# Sch_remote.net
KiCad netlist of a schematic drawn in Altium Designer
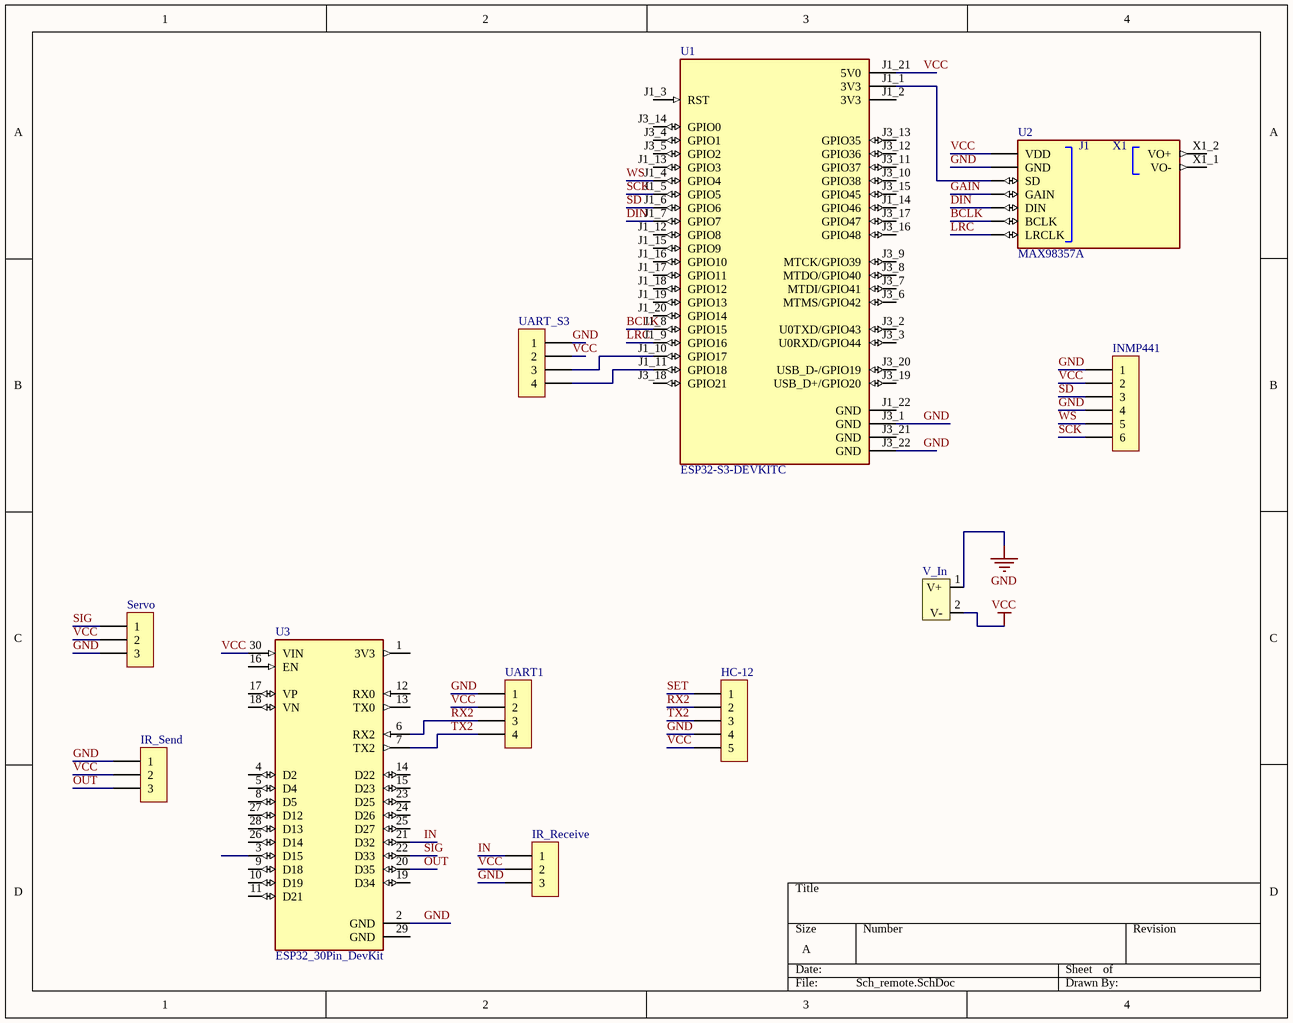
[diagram p0: Sch_remote.SchDoc]

(export (version "E")
  (design (tool "Eeschema 10.0.6"))
  (components
    (comp (ref "HC-12")
      (value "HC-12")
      (footprint "XH2.54M-5")
      (description "Cắm")
      (libsource (lib "Altium_Lib_by_KhueNguyenCreator") (part "Header 5P 2.54 Duc Thang"))
    )
    (comp (ref "INMP441")
      (value "INMP441")
      (footprint "XH2.54M-6")
      (description "Cắm")
      (libsource (lib "Altium_Lib_by_KhueNguyenCreator") (part "Header 6P 2.54 Duc Thang"))
    )
    (comp (ref "IR_Receive")
      (value "IR_Receive")
      (footprint "XH2.54M-3")
      (description "Cắm")
      (libsource (lib "Altium_Lib_by_KhueNguyenCreator") (part "Header 3P 2.54 Duc Thang"))
    )
    (comp (ref "IR_Send")
      (value "IR_Send")
      (footprint "XH2.54M-3")
      (description "Cắm")
      (libsource (lib "Altium_Lib_by_KhueNguyenCreator") (part "Header 3P 2.54 Duc Thang"))
    )
    (comp (ref "Servo")
      (value "Servo")
      (footprint "XH2.54M-3")
      (description "Cắm")
      (libsource (lib "Altium_Lib_by_KhueNguyenCreator") (part "Header 3P 2.54 Duc Thang"))
    )
    (comp (ref "U1")
      (value "ESP32-S3-DEVKITC")
      (footprint "ESP32_S3_DEV_KIT")
      (fields (field (name "MF") "Espressif Systems") (field (name "MP") "ESP32-S3-DEVKITC-1U-N8R8"))
      (libsource (lib "Schlib1") (part "ESP32-S3-DEVKITC"))
    )
    (comp (ref "U2")
      (value "MAX98357A")
      (footprint "MAX98357")
      (description "MAX98357A - 1-Channel (Mono) Output Class D Audio Amplifier Evaluation Board")
      (fields (field (name "MF") "Adafruit") (field (name "MP") "3006"))
      (libsource (lib "Schlib1") (part "MAX98357A"))
    )
    (comp (ref "U3")
      (value "ESP32_30Pin_DevKit")
      (footprint "MODULE_ESP32_DEVKIT_V1")
      (fields (field (name "MF") "Do it") (field (name "MP") "ESP32-DEVKIT-V1"))
      (libsource (lib "Schlib1") (part "ESP32_30Pin_DevKit"))
    )
    (comp (ref "UART1")
      (value "UART1")
      (footprint "Header 4P DC 2.54")
      (description "Cắm")
      (libsource (lib "Altium_Lib_by_KhueNguyenCreator") (part "Header 4P 2.54 Duc Cong"))
    )
    (comp (ref "UART_S3")
      (value "UART_S3")
      (footprint "Header 4P DC 2.54")
      (description "Cắm")
      (libsource (lib "") (part "Header 4P 2.54 Duc Cong_1"))
    )
    (comp (ref "V_In")
      (value "V_In")
      (footprint "header_2_power")
      (libsource (lib "Schlib1") (part "Header_2pin"))
    )
  )
  (nets
    (net (code "1") (name "/BCLK") (class "Default")
      (node (ref "U1") (pin "J1_8") (pinfunction "GPIO15_J1_8") (pintype "bidirectional"))
      (node (ref "U2") (pin "6") (pinfunction "BCLK_6") (pintype "bidirectional"))
    )
    (net (code "2") (name "/DIN") (class "Default")
      (node (ref "U1") (pin "J1_7") (pinfunction "GPIO7_J1_7") (pintype "bidirectional"))
      (node (ref "U2") (pin "5") (pinfunction "DIN_5") (pintype "bidirectional"))
    )
    (net (code "3") (name "/GAIN") (class "Default")
      (node (ref "U2") (pin "4") (pinfunction "GAIN_4") (pintype "bidirectional"))
    )
    (net (code "4") (name "/IN") (class "Default")
      (node (ref "IR_Receive") (pin "1") (pinfunction "1_1") (pintype "passive"))
      (node (ref "U3") (pin "21") (pinfunction "D32_21") (pintype "bidirectional"))
    )
    (net (code "5") (name "/LRC") (class "Default")
      (node (ref "U1") (pin "J1_9") (pinfunction "GPIO16_J1_9") (pintype "bidirectional"))
      (node (ref "U2") (pin "7") (pinfunction "LRCLK_7") (pintype "bidirectional"))
    )
    (net (code "6") (name "/OUT") (class "Default")
      (node (ref "IR_Send") (pin "3") (pinfunction "3_3") (pintype "passive"))
      (node (ref "U3") (pin "20") (pinfunction "D35_20") (pintype "bidirectional"))
    )
    (net (code "7") (name "/RX2") (class "Default")
      (node (ref "HC-12") (pin "2") (pinfunction "2_2") (pintype "passive"))
      (node (ref "U3") (pin "6") (pinfunction "RX2_6") (pintype "input"))
      (node (ref "UART1") (pin "3") (pinfunction "3_3") (pintype "passive"))
    )
    (net (code "8") (name "/SCK") (class "Default")
      (node (ref "INMP441") (pin "6") (pinfunction "6_6") (pintype "passive"))
      (node (ref "U1") (pin "J1_5") (pinfunction "GPIO5_J1_5") (pintype "bidirectional"))
    )
    (net (code "9") (name "/SD") (class "Default")
      (node (ref "INMP441") (pin "3") (pinfunction "3_3") (pintype "passive"))
      (node (ref "U1") (pin "J1_6") (pinfunction "GPIO6_J1_6") (pintype "bidirectional"))
    )
    (net (code "10") (name "/SET") (class "Default")
      (node (ref "HC-12") (pin "1") (pinfunction "1_1") (pintype "passive"))
    )
    (net (code "11") (name "/SIG") (class "Default")
      (node (ref "Servo") (pin "1") (pinfunction "1_1") (pintype "passive"))
      (node (ref "U3") (pin "22") (pinfunction "D33_22") (pintype "bidirectional"))
    )
    (net (code "12") (name "/TX2") (class "Default")
      (node (ref "HC-12") (pin "3") (pinfunction "3_3") (pintype "passive"))
      (node (ref "U3") (pin "7") (pinfunction "TX2_7") (pintype "output"))
      (node (ref "UART1") (pin "4") (pinfunction "4_4") (pintype "passive"))
    )
    (net (code "13") (name "/WS") (class "Default")
      (node (ref "INMP441") (pin "5") (pinfunction "5_5") (pintype "passive"))
      (node (ref "U1") (pin "J1_4") (pinfunction "GPIO4_J1_4") (pintype "bidirectional"))
    )
    (net (code "14") (name "GND") (class "Default")
      (node (ref "HC-12") (pin "4") (pinfunction "4_4") (pintype "passive"))
      (node (ref "INMP441") (pin "1") (pinfunction "1_1") (pintype "passive"))
      (node (ref "INMP441") (pin "4") (pinfunction "4_4") (pintype "passive"))
      (node (ref "IR_Receive") (pin "3") (pinfunction "3_3") (pintype "passive"))
      (node (ref "IR_Send") (pin "1") (pinfunction "1_1") (pintype "passive"))
      (node (ref "Servo") (pin "3") (pinfunction "3_3") (pintype "passive"))
      (node (ref "U1") (pin "J3_1") (pinfunction "GND_J3_1") (pintype "power_in"))
      (node (ref "U1") (pin "J3_22") (pinfunction "GND_J3_22") (pintype "power_in"))
      (node (ref "U2") (pin "2") (pinfunction "GND_2") (pintype "power_in"))
      (node (ref "U3") (pin "2") (pinfunction "GND_2") (pintype "power_in"))
      (node (ref "UART1") (pin "1") (pinfunction "1_1") (pintype "passive"))
      (node (ref "UART_S3") (pin "1") (pinfunction "1_1") (pintype "passive"))
      (node (ref "V_In") (pin "1") (pinfunction "V+_1") (pintype "bidirectional"))
    )
    (net (code "15") (name "Net-(U1-GPIO17)") (class "Default")
      (node (ref "U1") (pin "J1_10") (pinfunction "GPIO17_J1_10") (pintype "bidirectional"))
      (node (ref "UART_S3") (pin "3") (pinfunction "3_3") (pintype "passive"))
    )
    (net (code "16") (name "Net-(U1-GPIO18)") (class "Default")
      (node (ref "U1") (pin "J1_11") (pinfunction "GPIO18_J1_11") (pintype "bidirectional"))
      (node (ref "UART_S3") (pin "4") (pinfunction "4_4") (pintype "passive"))
    )
    (net (code "17") (name "Net-(U2-SD)") (class "Default")
      (node (ref "U1") (pin "J1_1") (pinfunction "3V3_J1_1") (pintype "power_in"))
      (node (ref "U2") (pin "3") (pinfunction "SD_3") (pintype "bidirectional"))
    )
    (net (code "18") (name "VCC") (class "Default")
      (node (ref "HC-12") (pin "5") (pinfunction "5_5") (pintype "passive"))
      (node (ref "INMP441") (pin "2") (pinfunction "2_2") (pintype "passive"))
      (node (ref "IR_Receive") (pin "2") (pinfunction "2_2") (pintype "passive"))
      (node (ref "IR_Send") (pin "2") (pinfunction "2_2") (pintype "passive"))
      (node (ref "Servo") (pin "2") (pinfunction "2_2") (pintype "passive"))
      (node (ref "U1") (pin "J1_21") (pinfunction "5V0_J1_21") (pintype "power_in"))
      (node (ref "U2") (pin "1") (pinfunction "VDD_1") (pintype "power_in"))
      (node (ref "U3") (pin "30") (pinfunction "VIN_30") (pintype "input"))
      (node (ref "UART1") (pin "2") (pinfunction "2_2") (pintype "passive"))
      (node (ref "UART_S3") (pin "2") (pinfunction "2_2") (pintype "passive"))
      (node (ref "V_In") (pin "2") (pinfunction "V-_2") (pintype "bidirectional"))
    )
    (net (code "19") (name "unconnected-(U1-3V3-PadJ1_2)") (class "Default")
      (node (ref "U1") (pin "J1_2") (pinfunction "3V3_J1_2") (pintype "power_in"))
    )
    (net (code "20") (name "unconnected-(U1-GND-PadJ1_22)") (class "Default")
      (node (ref "U1") (pin "J1_22") (pinfunction "GND_J1_22") (pintype "power_in"))
    )
    (net (code "21") (name "unconnected-(U1-GND-PadJ3_21)") (class "Default")
      (node (ref "U1") (pin "J3_21") (pinfunction "GND_J3_21") (pintype "power_in"))
    )
    (net (code "22") (name "unconnected-(U1-GPIO0-PadJ3_14)") (class "Default")
      (node (ref "U1") (pin "J3_14") (pinfunction "GPIO0_J3_14") (pintype "bidirectional"))
    )
    (net (code "23") (name "unconnected-(U1-GPIO1-PadJ3_4)") (class "Default")
      (node (ref "U1") (pin "J3_4") (pinfunction "GPIO1_J3_4") (pintype "bidirectional"))
    )
    (net (code "24") (name "unconnected-(U1-GPIO2-PadJ3_5)") (class "Default")
      (node (ref "U1") (pin "J3_5") (pinfunction "GPIO2_J3_5") (pintype "bidirectional"))
    )
    (net (code "25") (name "unconnected-(U1-GPIO3-PadJ1_13)") (class "Default")
      (node (ref "U1") (pin "J1_13") (pinfunction "GPIO3_J1_13") (pintype "bidirectional"))
    )
    (net (code "26") (name "unconnected-(U1-GPIO8-PadJ1_12)") (class "Default")
      (node (ref "U1") (pin "J1_12") (pinfunction "GPIO8_J1_12") (pintype "bidirectional"))
    )
    (net (code "27") (name "unconnected-(U1-GPIO9-PadJ1_15)") (class "Default")
      (node (ref "U1") (pin "J1_15") (pinfunction "GPIO9_J1_15") (pintype "bidirectional"))
    )
    (net (code "28") (name "unconnected-(U1-GPIO10-PadJ1_16)") (class "Default")
      (node (ref "U1") (pin "J1_16") (pinfunction "GPIO10_J1_16") (pintype "bidirectional"))
    )
    (net (code "29") (name "unconnected-(U1-GPIO11-PadJ1_17)") (class "Default")
      (node (ref "U1") (pin "J1_17") (pinfunction "GPIO11_J1_17") (pintype "bidirectional"))
    )
    (net (code "30") (name "unconnected-(U1-GPIO12-PadJ1_18)") (class "Default")
      (node (ref "U1") (pin "J1_18") (pinfunction "GPIO12_J1_18") (pintype "bidirectional"))
    )
    (net (code "31") (name "unconnected-(U1-GPIO13-PadJ1_19)") (class "Default")
      (node (ref "U1") (pin "J1_19") (pinfunction "GPIO13_J1_19") (pintype "bidirectional"))
    )
    (net (code "32") (name "unconnected-(U1-GPIO14-PadJ1_20)") (class "Default")
      (node (ref "U1") (pin "J1_20") (pinfunction "GPIO14_J1_20") (pintype "bidirectional"))
    )
    (net (code "33") (name "unconnected-(U1-GPIO21-PadJ3_18)") (class "Default")
      (node (ref "U1") (pin "J3_18") (pinfunction "GPIO21_J3_18") (pintype "bidirectional"))
    )
    (net (code "34") (name "unconnected-(U1-GPIO35-PadJ3_13)") (class "Default")
      (node (ref "U1") (pin "J3_13") (pinfunction "GPIO35_J3_13") (pintype "bidirectional"))
    )
    (net (code "35") (name "unconnected-(U1-GPIO36-PadJ3_12)") (class "Default")
      (node (ref "U1") (pin "J3_12") (pinfunction "GPIO36_J3_12") (pintype "bidirectional"))
    )
    (net (code "36") (name "unconnected-(U1-GPIO37-PadJ3_11)") (class "Default")
      (node (ref "U1") (pin "J3_11") (pinfunction "GPIO37_J3_11") (pintype "bidirectional"))
    )
    (net (code "37") (name "unconnected-(U1-GPIO38-PadJ3_10)") (class "Default")
      (node (ref "U1") (pin "J3_10") (pinfunction "GPIO38_J3_10") (pintype "bidirectional"))
    )
    (net (code "38") (name "unconnected-(U1-GPIO45-PadJ3_15)") (class "Default")
      (node (ref "U1") (pin "J3_15") (pinfunction "GPIO45_J3_15") (pintype "bidirectional"))
    )
    (net (code "39") (name "unconnected-(U1-GPIO46-PadJ1_14)") (class "Default")
      (node (ref "U1") (pin "J1_14") (pinfunction "GPIO46_J1_14") (pintype "bidirectional"))
    )
    (net (code "40") (name "unconnected-(U1-GPIO47-PadJ3_17)") (class "Default")
      (node (ref "U1") (pin "J3_17") (pinfunction "GPIO47_J3_17") (pintype "bidirectional"))
    )
    (net (code "41") (name "unconnected-(U1-GPIO48-PadJ3_16)") (class "Default")
      (node (ref "U1") (pin "J3_16") (pinfunction "GPIO48_J3_16") (pintype "bidirectional"))
    )
    (net (code "42") (name "unconnected-(U1-MTCK{slash}GPIO39-PadJ3_9)") (class "Default")
      (node (ref "U1") (pin "J3_9") (pinfunction "MTCK/GPIO39_J3_9") (pintype "bidirectional"))
    )
    (net (code "43") (name "unconnected-(U1-MTDI{slash}GPIO41-PadJ3_7)") (class "Default")
      (node (ref "U1") (pin "J3_7") (pinfunction "MTDI/GPIO41_J3_7") (pintype "bidirectional"))
    )
    (net (code "44") (name "unconnected-(U1-MTDO{slash}GPIO40-PadJ3_8)") (class "Default")
      (node (ref "U1") (pin "J3_8") (pinfunction "MTDO/GPIO40_J3_8") (pintype "bidirectional"))
    )
    (net (code "45") (name "unconnected-(U1-MTMS{slash}GPIO42-PadJ3_6)") (class "Default")
      (node (ref "U1") (pin "J3_6") (pinfunction "MTMS/GPIO42_J3_6") (pintype "bidirectional"))
    )
    (net (code "46") (name "unconnected-(U1-RST-PadJ1_3)") (class "Default")
      (node (ref "U1") (pin "J1_3") (pinfunction "RST_J1_3") (pintype "input"))
    )
    (net (code "47") (name "unconnected-(U1-U0RXD{slash}GPIO44-PadJ3_3)") (class "Default")
      (node (ref "U1") (pin "J3_3") (pinfunction "U0RXD/GPIO44_J3_3") (pintype "bidirectional"))
    )
    (net (code "48") (name "unconnected-(U1-U0TXD{slash}GPIO43-PadJ3_2)") (class "Default")
      (node (ref "U1") (pin "J3_2") (pinfunction "U0TXD/GPIO43_J3_2") (pintype "bidirectional"))
    )
    (net (code "49") (name "unconnected-(U1-USB_D+{slash}GPIO20-PadJ3_19)") (class "Default")
      (node (ref "U1") (pin "J3_19") (pinfunction "USB_D+/GPIO20_J3_19") (pintype "bidirectional"))
    )
    (net (code "50") (name "unconnected-(U1-USB_D-{slash}GPIO19-PadJ3_20)") (class "Default")
      (node (ref "U1") (pin "J3_20") (pinfunction "USB_D-/GPIO19_J3_20") (pintype "bidirectional"))
    )
    (net (code "51") (name "unconnected-(U2-VO+-PadX1_2)") (class "Default")
      (node (ref "U2") (pin "X1_2") (pinfunction "VO+_X1_2") (pintype "output"))
    )
    (net (code "52") (name "unconnected-(U2-VO--PadX1_1)") (class "Default")
      (node (ref "U2") (pin "X1_1") (pinfunction "VO-_X1_1") (pintype "output"))
    )
    (net (code "53") (name "unconnected-(U3-3V3-Pad1)") (class "Default")
      (node (ref "U3") (pin "1") (pinfunction "3V3_1") (pintype "output"))
    )
    (net (code "54") (name "unconnected-(U3-D2-Pad4)") (class "Default")
      (node (ref "U3") (pin "4") (pinfunction "D2_4") (pintype "bidirectional"))
    )
    (net (code "55") (name "unconnected-(U3-D4-Pad5)") (class "Default")
      (node (ref "U3") (pin "5") (pinfunction "D4_5") (pintype "bidirectional"))
    )
    (net (code "56") (name "unconnected-(U3-D5-Pad8)") (class "Default")
      (node (ref "U3") (pin "8") (pinfunction "D5_8") (pintype "bidirectional"))
    )
    (net (code "57") (name "unconnected-(U3-D12-Pad27)") (class "Default")
      (node (ref "U3") (pin "27") (pinfunction "D12_27") (pintype "bidirectional"))
    )
    (net (code "58") (name "unconnected-(U3-D13-Pad28)") (class "Default")
      (node (ref "U3") (pin "28") (pinfunction "D13_28") (pintype "bidirectional"))
    )
    (net (code "59") (name "unconnected-(U3-D14-Pad26)") (class "Default")
      (node (ref "U3") (pin "26") (pinfunction "D14_26") (pintype "bidirectional"))
    )
    (net (code "60") (name "unconnected-(U3-D15-Pad3)") (class "Default")
      (node (ref "U3") (pin "3") (pinfunction "D15_3") (pintype "bidirectional"))
    )
    (net (code "61") (name "unconnected-(U3-D18-Pad9)") (class "Default")
      (node (ref "U3") (pin "9") (pinfunction "D18_9") (pintype "bidirectional"))
    )
    (net (code "62") (name "unconnected-(U3-D19-Pad10)") (class "Default")
      (node (ref "U3") (pin "10") (pinfunction "D19_10") (pintype "bidirectional"))
    )
    (net (code "63") (name "unconnected-(U3-D21-Pad11)") (class "Default")
      (node (ref "U3") (pin "11") (pinfunction "D21_11") (pintype "bidirectional"))
    )
    (net (code "64") (name "unconnected-(U3-D22-Pad14)") (class "Default")
      (node (ref "U3") (pin "14") (pinfunction "D22_14") (pintype "bidirectional"))
    )
    (net (code "65") (name "unconnected-(U3-D23-Pad15)") (class "Default")
      (node (ref "U3") (pin "15") (pinfunction "D23_15") (pintype "bidirectional"))
    )
    (net (code "66") (name "unconnected-(U3-D25-Pad23)") (class "Default")
      (node (ref "U3") (pin "23") (pinfunction "D25_23") (pintype "bidirectional"))
    )
    (net (code "67") (name "unconnected-(U3-D26-Pad24)") (class "Default")
      (node (ref "U3") (pin "24") (pinfunction "D26_24") (pintype "bidirectional"))
    )
    (net (code "68") (name "unconnected-(U3-D27-Pad25)") (class "Default")
      (node (ref "U3") (pin "25") (pinfunction "D27_25") (pintype "bidirectional"))
    )
    (net (code "69") (name "unconnected-(U3-D34-Pad19)") (class "Default")
      (node (ref "U3") (pin "19") (pinfunction "D34_19") (pintype "bidirectional"))
    )
    (net (code "70") (name "unconnected-(U3-EN-Pad16)") (class "Default")
      (node (ref "U3") (pin "16") (pinfunction "EN_16") (pintype "input"))
    )
    (net (code "71") (name "unconnected-(U3-GND-Pad29)") (class "Default")
      (node (ref "U3") (pin "29") (pinfunction "GND_29") (pintype "power_in"))
    )
    (net (code "72") (name "unconnected-(U3-RX0-Pad12)") (class "Default")
      (node (ref "U3") (pin "12") (pinfunction "RX0_12") (pintype "input"))
    )
    (net (code "73") (name "unconnected-(U3-TX0-Pad13)") (class "Default")
      (node (ref "U3") (pin "13") (pinfunction "TX0_13") (pintype "output"))
    )
    (net (code "74") (name "unconnected-(U3-VN-Pad18)") (class "Default")
      (node (ref "U3") (pin "18") (pinfunction "VN_18") (pintype "bidirectional"))
    )
    (net (code "75") (name "unconnected-(U3-VP-Pad17)") (class "Default")
      (node (ref "U3") (pin "17") (pinfunction "VP_17") (pintype "bidirectional"))
    )
  )
)
